# relay.net
KiCad netlist of a schematic drawn in Altium Designer
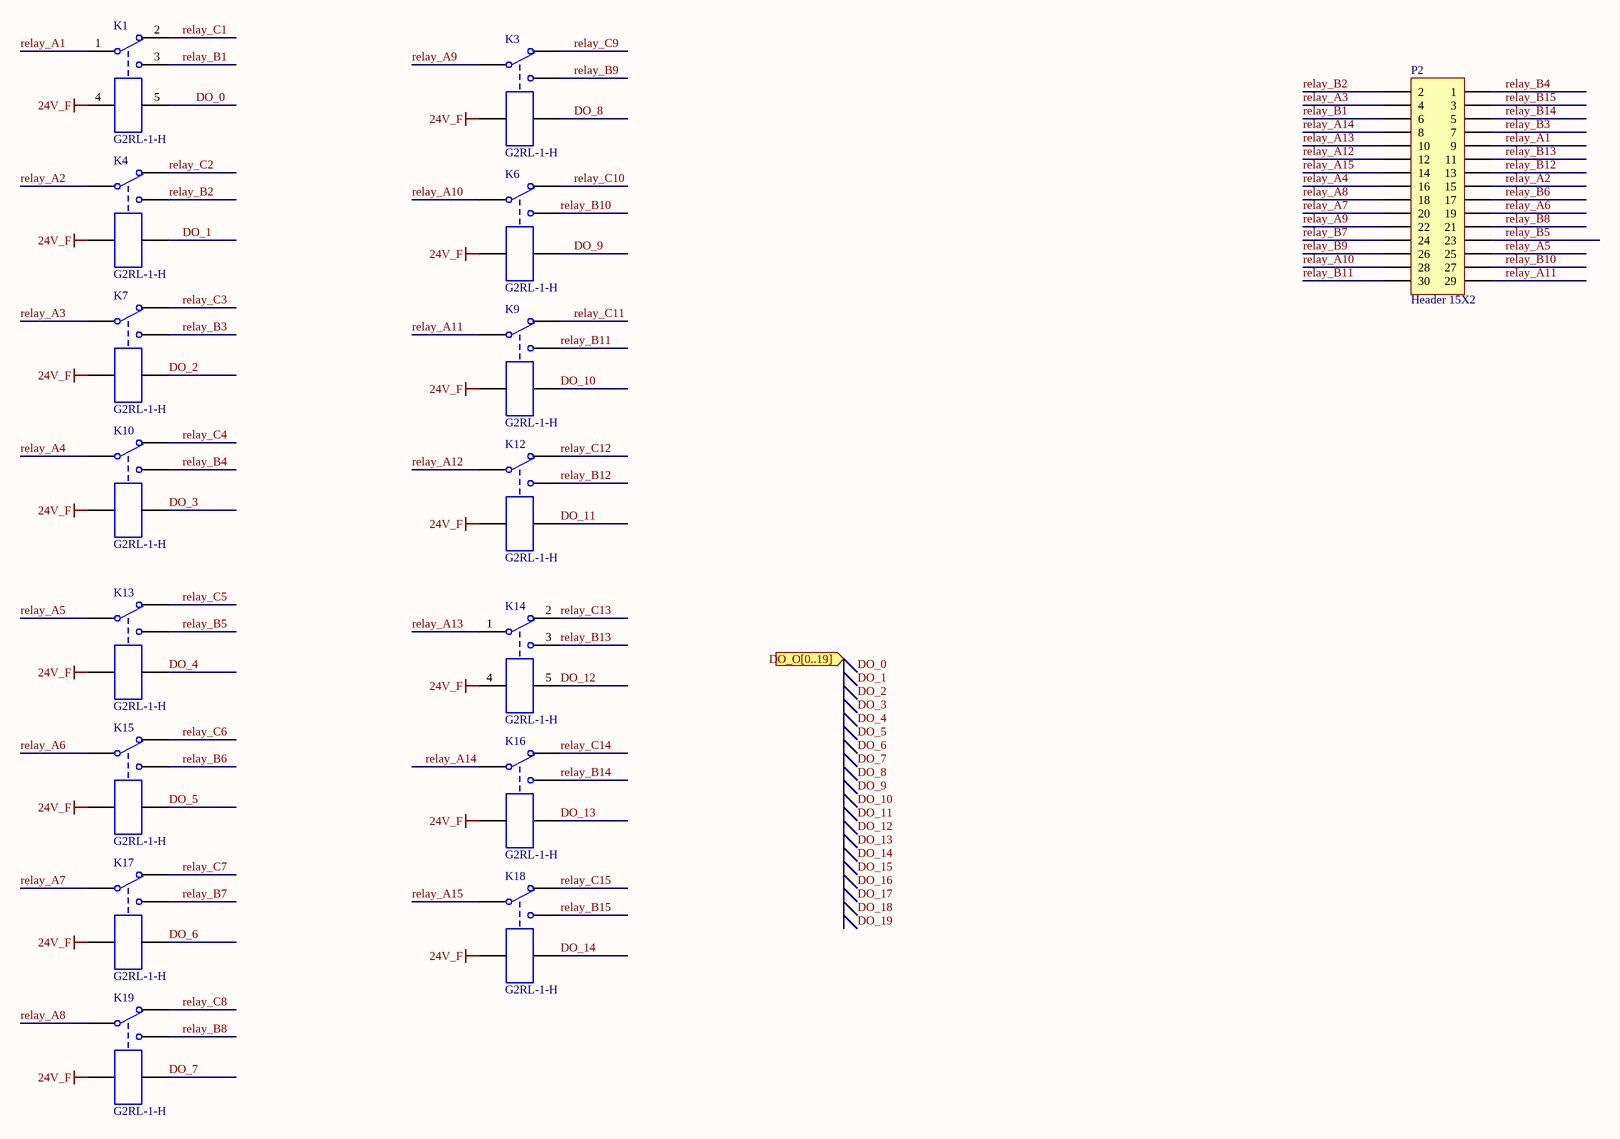
[diagram p0: relay.SchDoc]

(export (version "E")
  (design (tool "Eeschema 10.0.6"))
  (components
    (comp (ref "K1")
      (value "G2RL-1-H")
      (footprint "G2RL-1-H")
      (description "Single-Pole Dual-Throw Relay")
      (fields (field (name "PUBLISHER") "Altium Limited"))
      (libsource (lib "") (part "Relay-SPDT_1"))
    )
    (comp (ref "K3")
      (value "G2RL-1-H")
      (footprint "G2RL-1-H")
      (description "Single-Pole Dual-Throw Relay")
      (fields (field (name "PUBLISHER") "Altium Limited"))
      (libsource (lib "Miscellaneous Devices") (part "Relay-SPDT"))
    )
    (comp (ref "K4")
      (value "G2RL-1-H")
      (footprint "G2RL-1-H")
      (description "Single-Pole Dual-Throw Relay")
      (fields (field (name "PUBLISHER") "Altium Limited"))
      (libsource (lib "Miscellaneous Devices") (part "Relay-SPDT"))
    )
    (comp (ref "K6")
      (value "G2RL-1-H")
      (footprint "G2RL-1-H")
      (description "Single-Pole Dual-Throw Relay")
      (fields (field (name "PUBLISHER") "Altium Limited"))
      (libsource (lib "Miscellaneous Devices") (part "Relay-SPDT"))
    )
    (comp (ref "K7")
      (value "G2RL-1-H")
      (footprint "G2RL-1-H")
      (description "Single-Pole Dual-Throw Relay")
      (fields (field (name "PUBLISHER") "Altium Limited"))
      (libsource (lib "Miscellaneous Devices") (part "Relay-SPDT"))
    )
    (comp (ref "K9")
      (value "G2RL-1-H")
      (footprint "G2RL-1-H")
      (description "Single-Pole Dual-Throw Relay")
      (fields (field (name "PUBLISHER") "Altium Limited"))
      (libsource (lib "Miscellaneous Devices") (part "Relay-SPDT"))
    )
    (comp (ref "K10")
      (value "G2RL-1-H")
      (footprint "G2RL-1-H")
      (description "Single-Pole Dual-Throw Relay")
      (fields (field (name "PUBLISHER") "Altium Limited"))
      (libsource (lib "Miscellaneous Devices") (part "Relay-SPDT"))
    )
    (comp (ref "K12")
      (value "G2RL-1-H")
      (footprint "G2RL-1-H")
      (description "Single-Pole Dual-Throw Relay")
      (fields (field (name "PUBLISHER") "Altium Limited"))
      (libsource (lib "Miscellaneous Devices") (part "Relay-SPDT"))
    )
    (comp (ref "K13")
      (value "G2RL-1-H")
      (footprint "G2RL-1-H")
      (description "Single-Pole Dual-Throw Relay")
      (fields (field (name "PUBLISHER") "Altium Limited"))
      (libsource (lib "Miscellaneous Devices") (part "Relay-SPDT"))
    )
    (comp (ref "K14")
      (value "G2RL-1-H")
      (footprint "G2RL-1-H")
      (description "Single-Pole Dual-Throw Relay")
      (fields (field (name "PUBLISHER") "Altium Limited"))
      (libsource (lib "") (part "Relay-SPDT_1"))
    )
    (comp (ref "K15")
      (value "G2RL-1-H")
      (footprint "G2RL-1-H")
      (description "Single-Pole Dual-Throw Relay")
      (fields (field (name "PUBLISHER") "Altium Limited"))
      (libsource (lib "Miscellaneous Devices") (part "Relay-SPDT"))
    )
    (comp (ref "K16")
      (value "G2RL-1-H")
      (footprint "G2RL-1-H")
      (description "Single-Pole Dual-Throw Relay")
      (fields (field (name "PUBLISHER") "Altium Limited"))
      (libsource (lib "Miscellaneous Devices") (part "Relay-SPDT"))
    )
    (comp (ref "K17")
      (value "G2RL-1-H")
      (footprint "G2RL-1-H")
      (description "Single-Pole Dual-Throw Relay")
      (fields (field (name "PUBLISHER") "Altium Limited"))
      (libsource (lib "Miscellaneous Devices") (part "Relay-SPDT"))
    )
    (comp (ref "K18")
      (value "G2RL-1-H")
      (footprint "G2RL-1-H")
      (description "Single-Pole Dual-Throw Relay")
      (fields (field (name "PUBLISHER") "Altium Limited"))
      (libsource (lib "Miscellaneous Devices") (part "Relay-SPDT"))
    )
    (comp (ref "K19")
      (value "G2RL-1-H")
      (footprint "G2RL-1-H")
      (description "Single-Pole Dual-Throw Relay")
      (fields (field (name "PUBLISHER") "Altium Limited"))
      (libsource (lib "Miscellaneous Devices") (part "Relay-SPDT"))
    )
    (comp (ref "P2")
      (value "Header 15X2")
      (footprint "CONN-TH_30P-P2.50_KH-A2557-2X15A")
      (description "Header, 15-Pin, Dual row")
      (fields (field (name "PUBLISHER") "Altium Limited"))
      (libsource (lib "Miscellaneous Connectors") (part "Header 15X2"))
    )
  )
  (nets
    (net (code "21") (name "/DO_0") (class "Default")
      (node (ref "K1") (pin "5") (pinfunction "5_5") (pintype "passive"))
    )
    (net (code "22") (name "/DO_1") (class "Default")
      (node (ref "K4") (pin "5") (pinfunction "5_5") (pintype "passive"))
    )
    (net (code "23") (name "/DO_2") (class "Default")
      (node (ref "K7") (pin "5") (pinfunction "5_5") (pintype "passive"))
    )
    (net (code "24") (name "/DO_3") (class "Default")
      (node (ref "K10") (pin "5") (pinfunction "5_5") (pintype "passive"))
    )
    (net (code "25") (name "/DO_4") (class "Default")
      (node (ref "K13") (pin "5") (pinfunction "5_5") (pintype "passive"))
    )
    (net (code "26") (name "/DO_5") (class "Default")
      (node (ref "K15") (pin "5") (pinfunction "5_5") (pintype "passive"))
    )
    (net (code "27") (name "/DO_6") (class "Default")
      (node (ref "K17") (pin "5") (pinfunction "5_5") (pintype "passive"))
    )
    (net (code "28") (name "/DO_7") (class "Default")
      (node (ref "K19") (pin "5") (pinfunction "5_5") (pintype "passive"))
    )
    (net (code "29") (name "/DO_8") (class "Default")
      (node (ref "K3") (pin "5") (pinfunction "5_5") (pintype "passive"))
    )
    (net (code "30") (name "/DO_9") (class "Default")
      (node (ref "K6") (pin "5") (pinfunction "5_5") (pintype "passive"))
    )
    (net (code "31") (name "/DO_10") (class "Default")
      (node (ref "K9") (pin "5") (pinfunction "5_5") (pintype "passive"))
    )
    (net (code "32") (name "/DO_11") (class "Default")
      (node (ref "K12") (pin "5") (pinfunction "5_5") (pintype "passive"))
    )
    (net (code "33") (name "/DO_12") (class "Default")
      (node (ref "K14") (pin "5") (pinfunction "5_5") (pintype "passive"))
    )
    (net (code "34") (name "/DO_13") (class "Default")
      (node (ref "K16") (pin "5") (pinfunction "5_5") (pintype "passive"))
    )
    (net (code "35") (name "/DO_14") (class "Default")
      (node (ref "K18") (pin "5") (pinfunction "5_5") (pintype "passive"))
    )
    (net (code "42") (name "/relay_A1") (class "Default")
      (node (ref "K1") (pin "1") (pinfunction "1_1") (pintype "passive"))
      (node (ref "P2") (pin "9") (pinfunction "9_9") (pintype "passive"))
    )
    (net (code "43") (name "/relay_A2") (class "Default")
      (node (ref "K4") (pin "1") (pinfunction "1_1") (pintype "passive"))
      (node (ref "P2") (pin "15") (pinfunction "15_15") (pintype "passive"))
    )
    (net (code "44") (name "/relay_A3") (class "Default")
      (node (ref "K7") (pin "1") (pinfunction "1_1") (pintype "passive"))
      (node (ref "P2") (pin "4") (pinfunction "4_4") (pintype "passive"))
    )
    (net (code "45") (name "/relay_A4") (class "Default")
      (node (ref "K10") (pin "1") (pinfunction "1_1") (pintype "passive"))
      (node (ref "P2") (pin "16") (pinfunction "16_16") (pintype "passive"))
    )
    (net (code "46") (name "/relay_A5") (class "Default")
      (node (ref "K13") (pin "1") (pinfunction "1_1") (pintype "passive"))
      (node (ref "P2") (pin "25") (pinfunction "25_25") (pintype "passive"))
    )
    (net (code "47") (name "/relay_A6") (class "Default")
      (node (ref "K15") (pin "1") (pinfunction "1_1") (pintype "passive"))
      (node (ref "P2") (pin "19") (pinfunction "19_19") (pintype "passive"))
    )
    (net (code "48") (name "/relay_A7") (class "Default")
      (node (ref "K17") (pin "1") (pinfunction "1_1") (pintype "passive"))
      (node (ref "P2") (pin "20") (pinfunction "20_20") (pintype "passive"))
    )
    (net (code "49") (name "/relay_A8") (class "Default")
      (node (ref "K19") (pin "1") (pinfunction "1_1") (pintype "passive"))
      (node (ref "P2") (pin "18") (pinfunction "18_18") (pintype "passive"))
    )
    (net (code "50") (name "/relay_A9") (class "Default")
      (node (ref "K3") (pin "1") (pinfunction "1_1") (pintype "passive"))
      (node (ref "P2") (pin "22") (pinfunction "22_22") (pintype "passive"))
    )
    (net (code "51") (name "/relay_A10") (class "Default")
      (node (ref "K6") (pin "1") (pinfunction "1_1") (pintype "passive"))
      (node (ref "P2") (pin "28") (pinfunction "28_28") (pintype "passive"))
    )
    (net (code "52") (name "/relay_A11") (class "Default")
      (node (ref "K9") (pin "1") (pinfunction "1_1") (pintype "passive"))
      (node (ref "P2") (pin "29") (pinfunction "29_29") (pintype "passive"))
    )
    (net (code "53") (name "/relay_A12") (class "Default")
      (node (ref "K12") (pin "1") (pinfunction "1_1") (pintype "passive"))
      (node (ref "P2") (pin "12") (pinfunction "12_12") (pintype "passive"))
    )
    (net (code "54") (name "/relay_A13") (class "Default")
      (node (ref "K14") (pin "1") (pinfunction "1_1") (pintype "passive"))
      (node (ref "P2") (pin "10") (pinfunction "10_10") (pintype "passive"))
    )
    (net (code "55") (name "/relay_A14") (class "Default")
      (node (ref "K16") (pin "1") (pinfunction "1_1") (pintype "passive"))
      (node (ref "P2") (pin "8") (pinfunction "8_8") (pintype "passive"))
    )
    (net (code "56") (name "/relay_A15") (class "Default")
      (node (ref "K18") (pin "1") (pinfunction "1_1") (pintype "passive"))
      (node (ref "P2") (pin "14") (pinfunction "14_14") (pintype "passive"))
    )
    (net (code "57") (name "/relay_B1") (class "Default")
      (node (ref "K1") (pin "3") (pinfunction "3_3") (pintype "passive"))
      (node (ref "P2") (pin "6") (pinfunction "6_6") (pintype "passive"))
    )
    (net (code "58") (name "/relay_B2") (class "Default")
      (node (ref "K4") (pin "3") (pinfunction "3_3") (pintype "passive"))
      (node (ref "P2") (pin "2") (pinfunction "2_2") (pintype "passive"))
    )
    (net (code "59") (name "/relay_B3") (class "Default")
      (node (ref "K7") (pin "3") (pinfunction "3_3") (pintype "passive"))
      (node (ref "P2") (pin "7") (pinfunction "7_7") (pintype "passive"))
    )
    (net (code "60") (name "/relay_B4") (class "Default")
      (node (ref "K10") (pin "3") (pinfunction "3_3") (pintype "passive"))
      (node (ref "P2") (pin "1") (pinfunction "1_1") (pintype "passive"))
    )
    (net (code "61") (name "/relay_B5") (class "Default")
      (node (ref "K13") (pin "3") (pinfunction "3_3") (pintype "passive"))
      (node (ref "P2") (pin "23") (pinfunction "23_23") (pintype "passive"))
    )
    (net (code "62") (name "/relay_B6") (class "Default")
      (node (ref "K15") (pin "3") (pinfunction "3_3") (pintype "passive"))
      (node (ref "P2") (pin "17") (pinfunction "17_17") (pintype "passive"))
    )
    (net (code "63") (name "/relay_B7") (class "Default")
      (node (ref "K17") (pin "3") (pinfunction "3_3") (pintype "passive"))
      (node (ref "P2") (pin "24") (pinfunction "24_24") (pintype "passive"))
    )
    (net (code "64") (name "/relay_B8") (class "Default")
      (node (ref "K19") (pin "3") (pinfunction "3_3") (pintype "passive"))
      (node (ref "P2") (pin "21") (pinfunction "21_21") (pintype "passive"))
    )
    (net (code "65") (name "/relay_B9") (class "Default")
      (node (ref "K3") (pin "3") (pinfunction "3_3") (pintype "passive"))
      (node (ref "P2") (pin "26") (pinfunction "26_26") (pintype "passive"))
    )
    (net (code "66") (name "/relay_B10") (class "Default")
      (node (ref "K6") (pin "3") (pinfunction "3_3") (pintype "passive"))
      (node (ref "P2") (pin "27") (pinfunction "27_27") (pintype "passive"))
    )
    (net (code "67") (name "/relay_B11") (class "Default")
      (node (ref "K9") (pin "3") (pinfunction "3_3") (pintype "passive"))
      (node (ref "P2") (pin "30") (pinfunction "30_30") (pintype "passive"))
    )
    (net (code "68") (name "/relay_B12") (class "Default")
      (node (ref "K12") (pin "3") (pinfunction "3_3") (pintype "passive"))
      (node (ref "P2") (pin "13") (pinfunction "13_13") (pintype "passive"))
    )
    (net (code "69") (name "/relay_B13") (class "Default")
      (node (ref "K14") (pin "3") (pinfunction "3_3") (pintype "passive"))
      (node (ref "P2") (pin "11") (pinfunction "11_11") (pintype "passive"))
    )
    (net (code "70") (name "/relay_B14") (class "Default")
      (node (ref "K16") (pin "3") (pinfunction "3_3") (pintype "passive"))
      (node (ref "P2") (pin "5") (pinfunction "5_5") (pintype "passive"))
    )
    (net (code "71") (name "/relay_B15") (class "Default")
      (node (ref "K18") (pin "3") (pinfunction "3_3") (pintype "passive"))
      (node (ref "P2") (pin "3") (pinfunction "3_3") (pintype "passive"))
    )
    (net (code "72") (name "/relay_C1") (class "Default")
      (node (ref "K1") (pin "2") (pinfunction "2_2") (pintype "passive"))
    )
    (net (code "73") (name "/relay_C2") (class "Default")
      (node (ref "K4") (pin "2") (pinfunction "2_2") (pintype "passive"))
    )
    (net (code "74") (name "/relay_C3") (class "Default")
      (node (ref "K7") (pin "2") (pinfunction "2_2") (pintype "passive"))
    )
    (net (code "75") (name "/relay_C4") (class "Default")
      (node (ref "K10") (pin "2") (pinfunction "2_2") (pintype "passive"))
    )
    (net (code "76") (name "/relay_C5") (class "Default")
      (node (ref "K13") (pin "2") (pinfunction "2_2") (pintype "passive"))
    )
    (net (code "77") (name "/relay_C6") (class "Default")
      (node (ref "K15") (pin "2") (pinfunction "2_2") (pintype "passive"))
    )
    (net (code "78") (name "/relay_C7") (class "Default")
      (node (ref "K17") (pin "2") (pinfunction "2_2") (pintype "passive"))
    )
    (net (code "79") (name "/relay_C8") (class "Default")
      (node (ref "K19") (pin "2") (pinfunction "2_2") (pintype "passive"))
    )
    (net (code "80") (name "/relay_C9") (class "Default")
      (node (ref "K3") (pin "2") (pinfunction "2_2") (pintype "passive"))
    )
    (net (code "81") (name "/relay_C10") (class "Default")
      (node (ref "K6") (pin "2") (pinfunction "2_2") (pintype "passive"))
    )
    (net (code "82") (name "/relay_C11") (class "Default")
      (node (ref "K9") (pin "2") (pinfunction "2_2") (pintype "passive"))
    )
    (net (code "83") (name "/relay_C12") (class "Default")
      (node (ref "K12") (pin "2") (pinfunction "2_2") (pintype "passive"))
    )
    (net (code "84") (name "/relay_C13") (class "Default")
      (node (ref "K14") (pin "2") (pinfunction "2_2") (pintype "passive"))
    )
    (net (code "85") (name "/relay_C14") (class "Default")
      (node (ref "K16") (pin "2") (pinfunction "2_2") (pintype "passive"))
    )
    (net (code "86") (name "/relay_C15") (class "Default")
      (node (ref "K18") (pin "2") (pinfunction "2_2") (pintype "passive"))
    )
    (net (code "87") (name "24V_F") (class "Default")
      (node (ref "K1") (pin "4") (pinfunction "4_4") (pintype "passive"))
      (node (ref "K10") (pin "4") (pinfunction "4_4") (pintype "passive"))
      (node (ref "K12") (pin "4") (pinfunction "4_4") (pintype "passive"))
      (node (ref "K13") (pin "4") (pinfunction "4_4") (pintype "passive"))
      (node (ref "K14") (pin "4") (pinfunction "4_4") (pintype "passive"))
      (node (ref "K15") (pin "4") (pinfunction "4_4") (pintype "passive"))
      (node (ref "K16") (pin "4") (pinfunction "4_4") (pintype "passive"))
      (node (ref "K17") (pin "4") (pinfunction "4_4") (pintype "passive"))
      (node (ref "K18") (pin "4") (pinfunction "4_4") (pintype "passive"))
      (node (ref "K19") (pin "4") (pinfunction "4_4") (pintype "passive"))
      (node (ref "K3") (pin "4") (pinfunction "4_4") (pintype "passive"))
      (node (ref "K4") (pin "4") (pinfunction "4_4") (pintype "passive"))
      (node (ref "K6") (pin "4") (pinfunction "4_4") (pintype "passive"))
      (node (ref "K7") (pin "4") (pinfunction "4_4") (pintype "passive"))
      (node (ref "K9") (pin "4") (pinfunction "4_4") (pintype "passive"))
    )
  )
)
